# keybint.net
KiCad netlist of a schematic drawn in EAGLE
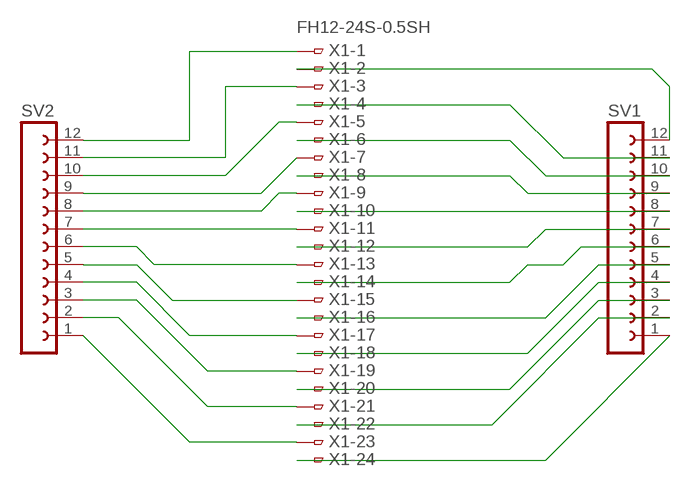
[diagram p0: schematic, sheet 1]

(export (version "E")
  (design (tool "Eeschema 10.0.6"))
  (components
    (comp (ref "SV1")
      (value "FE12-1")
      (footprint "eagle-import:FE12")
      (libsource (lib "eagle-import") (part "FE12-1"))
    )
    (comp (ref "SV2")
      (value "FE12-1")
      (footprint "eagle-import:FE12")
      (libsource (lib "eagle-import") (part "FE12-1"))
    )
    (comp (ref "X1")
      (value "FH12-24S-0.5SH")
      (footprint "eagle-import:FH12-24S-0.5SH")
      (fields (field (name "MPN") "FH12-24S-0.5SH(55)"))
      (libsource (lib "eagle-import") (part "FH12-24S-0.5SH"))
    )
  )
  (nets
    (net (code "1") (name "Net-(SV2-Pad12)") (class "Default")
      (node (ref "SV2") (pin "12") (pinfunction "12_12") (pintype "passive"))
      (node (ref "X1") (pin "1") (pinfunction "1_1") (pintype "passive"))
    )
    (net (code "2") (name "Net-(X1B-1)") (class "Default")
      (node (ref "SV1") (pin "8") (pinfunction "8_8") (pintype "passive"))
      (node (ref "X1") (pin "10") (pinfunction "1_10") (pintype "passive"))
    )
    (net (code "3") (name "Net-(X1C-1)") (class "Default")
      (node (ref "SV2") (pin "7") (pinfunction "7_7") (pintype "passive"))
      (node (ref "X1") (pin "11") (pinfunction "1_11") (pintype "passive"))
    )
    (net (code "4") (name "Net-(X1D-1)") (class "Default")
      (node (ref "SV1") (pin "7") (pinfunction "7_7") (pintype "passive"))
      (node (ref "X1") (pin "12") (pinfunction "1_12") (pintype "passive"))
    )
    (net (code "5") (name "Net-(X1E-1)") (class "Default")
      (node (ref "SV2") (pin "6") (pinfunction "6_6") (pintype "passive"))
      (node (ref "X1") (pin "13") (pinfunction "1_13") (pintype "passive"))
    )
    (net (code "6") (name "Net-(X1F-1)") (class "Default")
      (node (ref "SV1") (pin "6") (pinfunction "6_6") (pintype "passive"))
      (node (ref "X1") (pin "14") (pinfunction "1_14") (pintype "passive"))
    )
    (net (code "7") (name "Net-(X1G-1)") (class "Default")
      (node (ref "SV2") (pin "5") (pinfunction "5_5") (pintype "passive"))
      (node (ref "X1") (pin "15") (pinfunction "1_15") (pintype "passive"))
    )
    (net (code "8") (name "Net-(X1H-1)") (class "Default")
      (node (ref "SV1") (pin "5") (pinfunction "5_5") (pintype "passive"))
      (node (ref "X1") (pin "16") (pinfunction "1_16") (pintype "passive"))
    )
    (net (code "9") (name "Net-(X1I-1)") (class "Default")
      (node (ref "SV2") (pin "4") (pinfunction "4_4") (pintype "passive"))
      (node (ref "X1") (pin "17") (pinfunction "1_17") (pintype "passive"))
    )
    (net (code "10") (name "Net-(X1J-1)") (class "Default")
      (node (ref "SV1") (pin "4") (pinfunction "4_4") (pintype "passive"))
      (node (ref "X1") (pin "18") (pinfunction "1_18") (pintype "passive"))
    )
    (net (code "11") (name "Net-(X1K-1)") (class "Default")
      (node (ref "SV2") (pin "3") (pinfunction "3_3") (pintype "passive"))
      (node (ref "X1") (pin "19") (pinfunction "1_19") (pintype "passive"))
    )
    (net (code "12") (name "Net-(X1L-1)") (class "Default")
      (node (ref "SV1") (pin "12") (pinfunction "12_12") (pintype "passive"))
      (node (ref "X1") (pin "2") (pinfunction "1_2") (pintype "passive"))
    )
    (net (code "13") (name "Net-(X1M-1)") (class "Default")
      (node (ref "SV1") (pin "3") (pinfunction "3_3") (pintype "passive"))
      (node (ref "X1") (pin "20") (pinfunction "1_20") (pintype "passive"))
    )
    (net (code "14") (name "Net-(X1N-1)") (class "Default")
      (node (ref "SV2") (pin "2") (pinfunction "2_2") (pintype "passive"))
      (node (ref "X1") (pin "21") (pinfunction "1_21") (pintype "passive"))
    )
    (net (code "15") (name "Net-(X1O-1)") (class "Default")
      (node (ref "SV1") (pin "2") (pinfunction "2_2") (pintype "passive"))
      (node (ref "X1") (pin "22") (pinfunction "1_22") (pintype "passive"))
    )
    (net (code "16") (name "Net-(X1P-1)") (class "Default")
      (node (ref "SV2") (pin "1") (pinfunction "1_1") (pintype "passive"))
      (node (ref "X1") (pin "23") (pinfunction "1_23") (pintype "passive"))
    )
    (net (code "17") (name "Net-(X1Q-1)") (class "Default")
      (node (ref "SV1") (pin "1") (pinfunction "1_1") (pintype "passive"))
      (node (ref "X1") (pin "24") (pinfunction "1_24") (pintype "passive"))
    )
    (net (code "18") (name "Net-(X1R-1)") (class "Default")
      (node (ref "SV2") (pin "11") (pinfunction "11_11") (pintype "passive"))
      (node (ref "X1") (pin "3") (pinfunction "1_3") (pintype "passive"))
    )
    (net (code "19") (name "Net-(X1S-1)") (class "Default")
      (node (ref "SV1") (pin "11") (pinfunction "11_11") (pintype "passive"))
      (node (ref "X1") (pin "4") (pinfunction "1_4") (pintype "passive"))
    )
    (net (code "20") (name "Net-(X1T-1)") (class "Default")
      (node (ref "SV2") (pin "10") (pinfunction "10_10") (pintype "passive"))
      (node (ref "X1") (pin "5") (pinfunction "1_5") (pintype "passive"))
    )
    (net (code "21") (name "Net-(X1U-1)") (class "Default")
      (node (ref "SV1") (pin "10") (pinfunction "10_10") (pintype "passive"))
      (node (ref "X1") (pin "6") (pinfunction "1_6") (pintype "passive"))
    )
    (net (code "22") (name "Net-(X1V-1)") (class "Default")
      (node (ref "SV2") (pin "9") (pinfunction "9_9") (pintype "passive"))
      (node (ref "X1") (pin "7") (pinfunction "1_7") (pintype "passive"))
    )
    (net (code "23") (name "Net-(X1W-1)") (class "Default")
      (node (ref "SV1") (pin "9") (pinfunction "9_9") (pintype "passive"))
      (node (ref "X1") (pin "8") (pinfunction "1_8") (pintype "passive"))
    )
    (net (code "24") (name "Net-(X1X-1)") (class "Default")
      (node (ref "SV2") (pin "8") (pinfunction "8_8") (pintype "passive"))
      (node (ref "X1") (pin "9") (pinfunction "1_9") (pintype "passive"))
    )
  )
)
